# dashboard.net
KiCad netlist of a schematic drawn in EAGLE
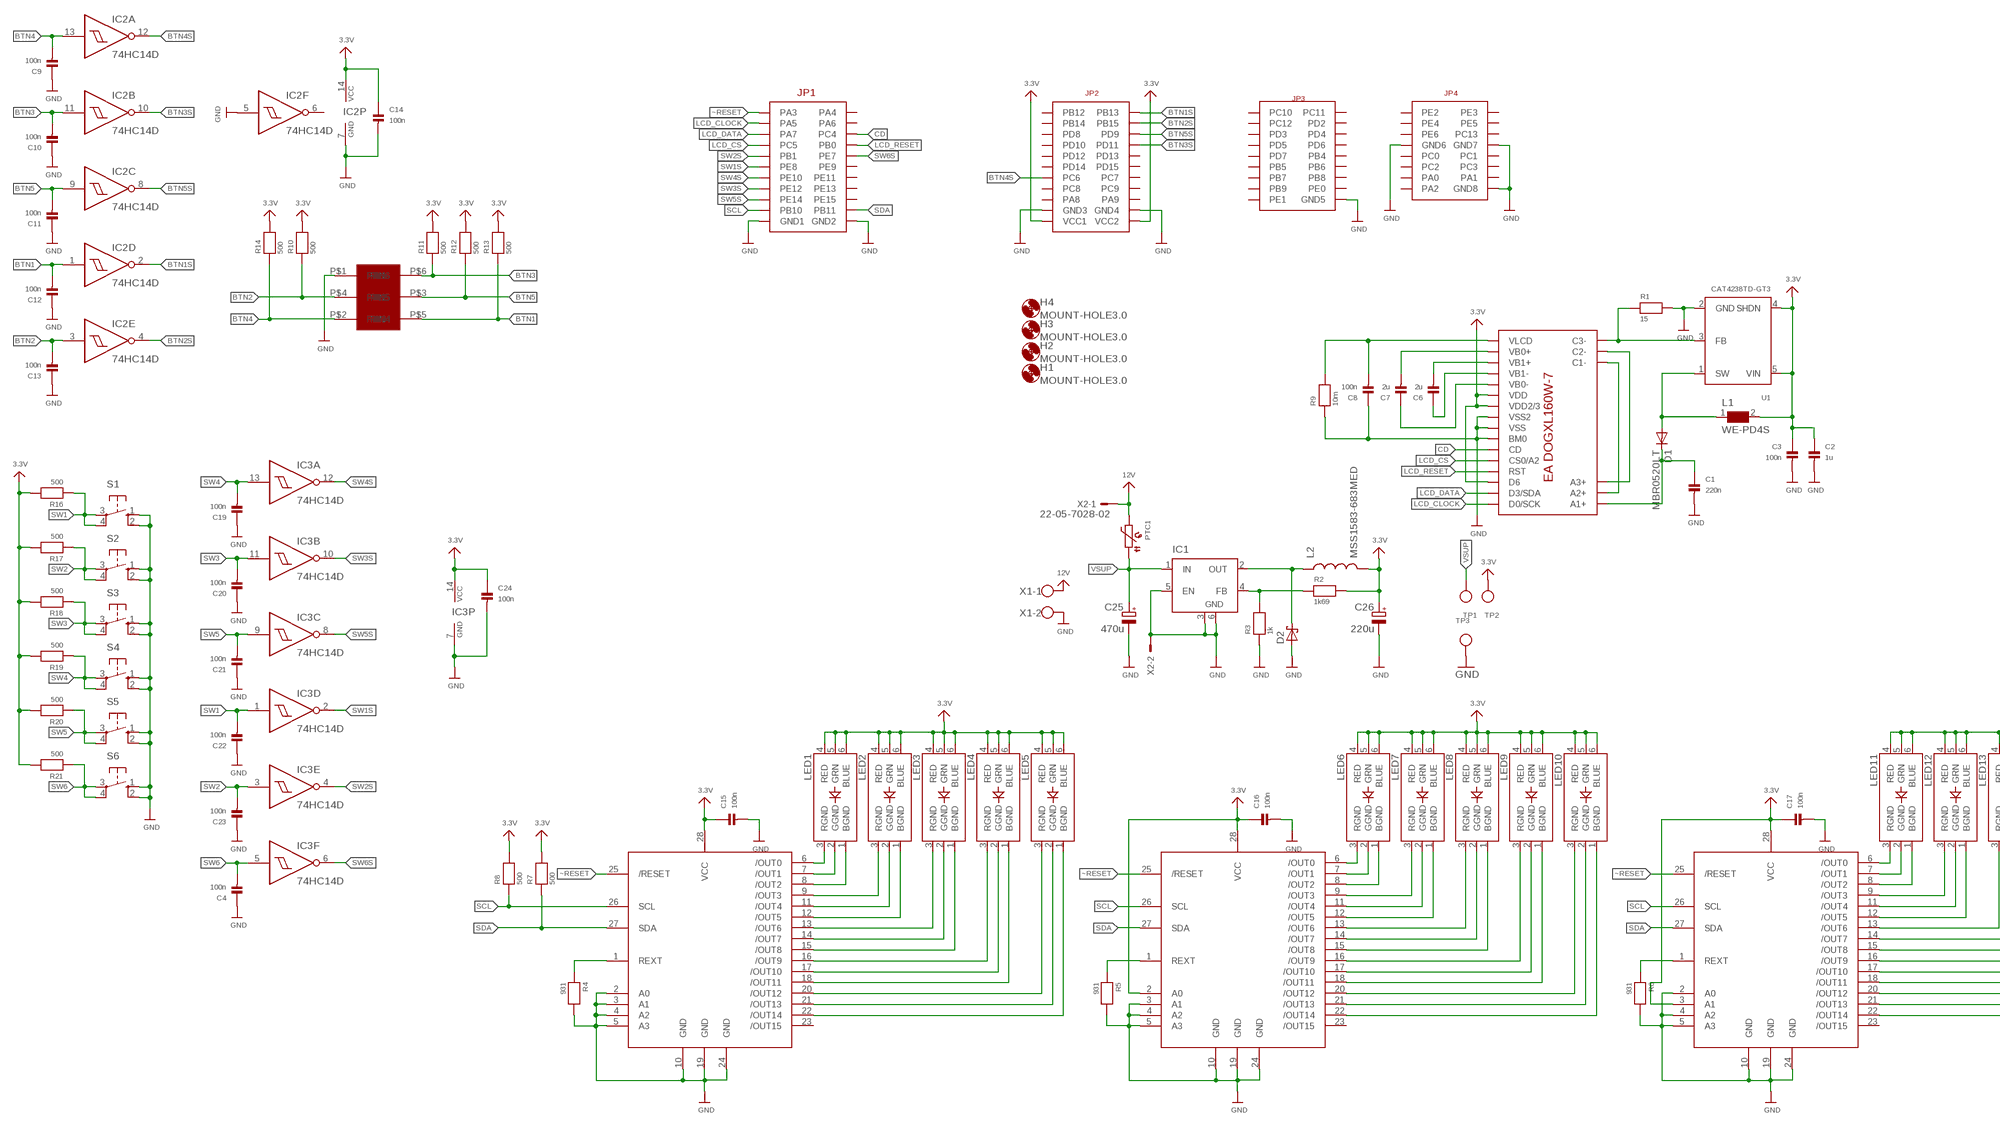
[diagram p0: schematic, sheet 1, part 1 of 2]
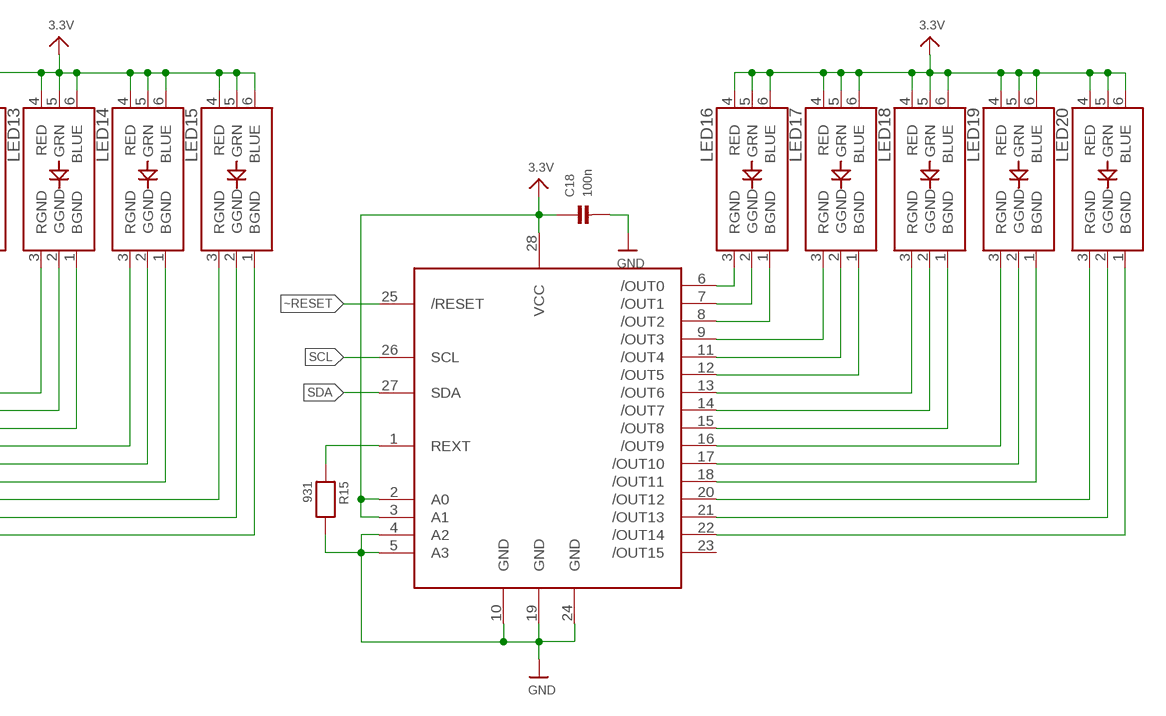
[diagram p1: schematic, sheet 1, part 2 of 2]

(export (version "E")
  (design (tool "Eeschema 10.0.6"))
  (components
    (comp (ref "C1")
      (value "220n")
      (footprint "eagle-import:_0805")
      (libsource (lib "eagle-import") (part "CAP_CERAMIC_0805"))
    )
    (comp (ref "C2")
      (value "1u")
      (footprint "eagle-import:_0805")
      (libsource (lib "eagle-import") (part "CAP_CERAMIC_0805"))
    )
    (comp (ref "C3")
      (value "100n")
      (footprint "eagle-import:_0603")
      (libsource (lib "eagle-import") (part "CAP_CERAMIC_0603"))
    )
    (comp (ref "C4")
      (value "100n")
      (footprint "eagle-import:_0603")
      (libsource (lib "eagle-import") (part "CAP_CERAMIC_0603"))
    )
    (comp (ref "C6")
      (value "2u")
      (footprint "eagle-import:_0805")
      (libsource (lib "eagle-import") (part "CAP_CERAMIC_0805"))
    )
    (comp (ref "C7")
      (value "2u")
      (footprint "eagle-import:_0805")
      (libsource (lib "eagle-import") (part "CAP_CERAMIC_0805"))
    )
    (comp (ref "C8")
      (value "100n")
      (footprint "eagle-import:_0603")
      (libsource (lib "eagle-import") (part "CAP_CERAMIC_0603"))
    )
    (comp (ref "C9")
      (value "100n")
      (footprint "eagle-import:_0603")
      (libsource (lib "eagle-import") (part "CAP_CERAMIC_0603"))
    )
    (comp (ref "C10")
      (value "100n")
      (footprint "eagle-import:_0603")
      (libsource (lib "eagle-import") (part "CAP_CERAMIC_0603"))
    )
    (comp (ref "C11")
      (value "100n")
      (footprint "eagle-import:_0603")
      (libsource (lib "eagle-import") (part "CAP_CERAMIC_0603"))
    )
    (comp (ref "C12")
      (value "100n")
      (footprint "eagle-import:_0603")
      (libsource (lib "eagle-import") (part "CAP_CERAMIC_0603"))
    )
    (comp (ref "C13")
      (value "100n")
      (footprint "eagle-import:_0603")
      (libsource (lib "eagle-import") (part "CAP_CERAMIC_0603"))
    )
    (comp (ref "C14")
      (value "100n")
      (footprint "eagle-import:_0603")
      (libsource (lib "eagle-import") (part "CAP_CERAMIC_0603"))
    )
    (comp (ref "C15")
      (value "100n")
      (footprint "eagle-import:_0603")
      (libsource (lib "eagle-import") (part "CAP_CERAMIC_0603"))
    )
    (comp (ref "C16")
      (value "100n")
      (footprint "eagle-import:_0603")
      (libsource (lib "eagle-import") (part "CAP_CERAMIC_0603"))
    )
    (comp (ref "C17")
      (value "100n")
      (footprint "eagle-import:_0603")
      (libsource (lib "eagle-import") (part "CAP_CERAMIC_0603"))
    )
    (comp (ref "C18")
      (value "100n")
      (footprint "eagle-import:_0603")
      (libsource (lib "eagle-import") (part "CAP_CERAMIC_0603"))
    )
    (comp (ref "C19")
      (value "100n")
      (footprint "eagle-import:_0603")
      (libsource (lib "eagle-import") (part "CAP_CERAMIC_0603"))
    )
    (comp (ref "C20")
      (value "100n")
      (footprint "eagle-import:_0603")
      (libsource (lib "eagle-import") (part "CAP_CERAMIC_0603"))
    )
    (comp (ref "C21")
      (value "100n")
      (footprint "eagle-import:_0603")
      (libsource (lib "eagle-import") (part "CAP_CERAMIC_0603"))
    )
    (comp (ref "C22")
      (value "100n")
      (footprint "eagle-import:_0603")
      (libsource (lib "eagle-import") (part "CAP_CERAMIC_0603"))
    )
    (comp (ref "C23")
      (value "100n")
      (footprint "eagle-import:_0603")
      (libsource (lib "eagle-import") (part "CAP_CERAMIC_0603"))
    )
    (comp (ref "C24")
      (value "100n")
      (footprint "eagle-import:_0603")
      (libsource (lib "eagle-import") (part "CAP_CERAMIC_0603"))
    )
    (comp (ref "C25")
      (value "470u")
      (footprint "eagle-import:153CLV-1012")
      (libsource (lib "eagle-import") (part "CPOL-EU153CLV-1012"))
    )
    (comp (ref "C26")
      (value "220u")
      (footprint "eagle-import:153CLV-1012")
      (libsource (lib "eagle-import") (part "CPOL-EU153CLV-1012"))
    )
    (comp (ref "D1")
      (value "MBR0520LT")
      (footprint "eagle-import:SOD123")
      (libsource (lib "eagle-import") (part "MBR0520LT"))
    )
    (comp (ref "D2")
      (value "SCHOTTKY-DIODESMC")
      (footprint "eagle-import:SMC")
      (libsource (lib "eagle-import") (part "SCHOTTKY-DIODESMC"))
    )
    (comp (ref "H1")
      (value "MOUNT-HOLE3.0")
      (footprint "eagle-import:3,0")
      (libsource (lib "eagle-import") (part "MOUNT-HOLE3.0"))
    )
    (comp (ref "H2")
      (value "MOUNT-HOLE3.0")
      (footprint "eagle-import:3,0")
      (libsource (lib "eagle-import") (part "MOUNT-HOLE3.0"))
    )
    (comp (ref "H3")
      (value "MOUNT-HOLE3.0")
      (footprint "eagle-import:3,0")
      (libsource (lib "eagle-import") (part "MOUNT-HOLE3.0"))
    )
    (comp (ref "H4")
      (value "MOUNT-HOLE3.0")
      (footprint "eagle-import:3,0")
      (libsource (lib "eagle-import") (part "MOUNT-HOLE3.0"))
    )
    (comp (ref "IC1")
      (value "LM2596S")
      (footprint "eagle-import:TO263-5")
      (libsource (lib "eagle-import") (part "LM2596S"))
    )
    (comp (ref "IC2")
      (value "74HC14D")
      (footprint "eagle-import:SO14")
      (libsource (lib "eagle-import") (part "7414DHC"))
    )
    (comp (ref "IC3")
      (value "74HC14D")
      (footprint "eagle-import:SO14")
      (libsource (lib "eagle-import") (part "7414DHC"))
    )
    (comp (ref "L1")
      (value "WE-PD4S")
      (footprint "eagle-import:S")
      (fields (field (name "MPN") "7445501"))
      (libsource (lib "eagle-import") (part "WE-PD4_S-7445501"))
    )
    (comp (ref "L2")
      (value "MSS1583-683MED")
      (footprint "eagle-import:CDRH125")
      (libsource (lib "eagle-import") (part "INDUCTORPWR"))
    )
    (comp (ref "LED1")
      (value "LED_RGB_PLCC6CREE-CLV6A")
      (footprint "eagle-import:RGBLED_PLCC6")
      (libsource (lib "eagle-import") (part "LED_RGB_PLCC6CREE-CLV6A"))
    )
    (comp (ref "LED2")
      (value "LED_RGB_PLCC6CREE-CLV6A")
      (footprint "eagle-import:RGBLED_PLCC6")
      (libsource (lib "eagle-import") (part "LED_RGB_PLCC6CREE-CLV6A"))
    )
    (comp (ref "LED3")
      (value "LED_RGB_PLCC6CREE-CLV6A")
      (footprint "eagle-import:RGBLED_PLCC6")
      (libsource (lib "eagle-import") (part "LED_RGB_PLCC6CREE-CLV6A"))
    )
    (comp (ref "LED4")
      (value "LED_RGB_PLCC6CREE-CLV6A")
      (footprint "eagle-import:RGBLED_PLCC6")
      (libsource (lib "eagle-import") (part "LED_RGB_PLCC6CREE-CLV6A"))
    )
    (comp (ref "LED5")
      (value "LED_RGB_PLCC6CREE-CLV6A")
      (footprint "eagle-import:RGBLED_PLCC6")
      (libsource (lib "eagle-import") (part "LED_RGB_PLCC6CREE-CLV6A"))
    )
    (comp (ref "LED6")
      (value "LED_RGB_PLCC6CREE-CLV6A")
      (footprint "eagle-import:RGBLED_PLCC6")
      (libsource (lib "eagle-import") (part "LED_RGB_PLCC6CREE-CLV6A"))
    )
    (comp (ref "LED7")
      (value "LED_RGB_PLCC6CREE-CLV6A")
      (footprint "eagle-import:RGBLED_PLCC6")
      (libsource (lib "eagle-import") (part "LED_RGB_PLCC6CREE-CLV6A"))
    )
    (comp (ref "LED8")
      (value "LED_RGB_PLCC6CREE-CLV6A")
      (footprint "eagle-import:RGBLED_PLCC6")
      (libsource (lib "eagle-import") (part "LED_RGB_PLCC6CREE-CLV6A"))
    )
    (comp (ref "LED9")
      (value "LED_RGB_PLCC6CREE-CLV6A")
      (footprint "eagle-import:RGBLED_PLCC6")
      (libsource (lib "eagle-import") (part "LED_RGB_PLCC6CREE-CLV6A"))
    )
    (comp (ref "LED10")
      (value "LED_RGB_PLCC6CREE-CLV6A")
      (footprint "eagle-import:RGBLED_PLCC6")
      (libsource (lib "eagle-import") (part "LED_RGB_PLCC6CREE-CLV6A"))
    )
    (comp (ref "LED11")
      (value "LED_RGB_PLCC6CREE-CLV6A")
      (footprint "eagle-import:RGBLED_PLCC6")
      (libsource (lib "eagle-import") (part "LED_RGB_PLCC6CREE-CLV6A"))
    )
    (comp (ref "LED12")
      (value "LED_RGB_PLCC6CREE-CLV6A")
      (footprint "eagle-import:RGBLED_PLCC6")
      (libsource (lib "eagle-import") (part "LED_RGB_PLCC6CREE-CLV6A"))
    )
    (comp (ref "LED13")
      (value "LED_RGB_PLCC6CREE-CLV6A")
      (footprint "eagle-import:RGBLED_PLCC6")
      (libsource (lib "eagle-import") (part "LED_RGB_PLCC6CREE-CLV6A"))
    )
    (comp (ref "LED14")
      (value "LED_RGB_PLCC6CREE-CLV6A")
      (footprint "eagle-import:RGBLED_PLCC6")
      (libsource (lib "eagle-import") (part "LED_RGB_PLCC6CREE-CLV6A"))
    )
    (comp (ref "LED15")
      (value "LED_RGB_PLCC6CREE-CLV6A")
      (footprint "eagle-import:RGBLED_PLCC6")
      (libsource (lib "eagle-import") (part "LED_RGB_PLCC6CREE-CLV6A"))
    )
    (comp (ref "LED16")
      (value "LED_RGB_PLCC6CREE-CLV6A")
      (footprint "eagle-import:RGBLED_PLCC6")
      (libsource (lib "eagle-import") (part "LED_RGB_PLCC6CREE-CLV6A"))
    )
    (comp (ref "LED17")
      (value "LED_RGB_PLCC6CREE-CLV6A")
      (footprint "eagle-import:RGBLED_PLCC6")
      (libsource (lib "eagle-import") (part "LED_RGB_PLCC6CREE-CLV6A"))
    )
    (comp (ref "LED18")
      (value "LED_RGB_PLCC6CREE-CLV6A")
      (footprint "eagle-import:RGBLED_PLCC6")
      (libsource (lib "eagle-import") (part "LED_RGB_PLCC6CREE-CLV6A"))
    )
    (comp (ref "LED19")
      (value "LED_RGB_PLCC6CREE-CLV6A")
      (footprint "eagle-import:RGBLED_PLCC6")
      (libsource (lib "eagle-import") (part "LED_RGB_PLCC6CREE-CLV6A"))
    )
    (comp (ref "LED20")
      (value "LED_RGB_PLCC6CREE-CLV6A")
      (footprint "eagle-import:RGBLED_PLCC6")
      (libsource (lib "eagle-import") (part "LED_RGB_PLCC6CREE-CLV6A"))
    )
    (comp (ref "PTC1")
      (value "PTC1812")
      (footprint "eagle-import:PTC1812")
      (libsource (lib "eagle-import") (part "PTC1812"))
    )
    (comp (ref "R1")
      (value "15")
      (footprint "eagle-import:_0603")
      (libsource (lib "eagle-import") (part "RESISTOR_0603"))
    )
    (comp (ref "R2")
      (value "1k69")
      (footprint "eagle-import:_0603")
      (libsource (lib "eagle-import") (part "RESISTOR_0603"))
    )
    (comp (ref "R3")
      (value "1k")
      (footprint "eagle-import:_0603")
      (libsource (lib "eagle-import") (part "RESISTOR_0603"))
    )
    (comp (ref "R4")
      (value "931")
      (footprint "eagle-import:_0603")
      (libsource (lib "eagle-import") (part "RESISTOR_0603"))
    )
    (comp (ref "R5")
      (value "931")
      (footprint "eagle-import:_0603")
      (libsource (lib "eagle-import") (part "RESISTOR_0603"))
    )
    (comp (ref "R6")
      (value "931")
      (footprint "eagle-import:_0603")
      (libsource (lib "eagle-import") (part "RESISTOR_0603"))
    )
    (comp (ref "R7")
      (value "500")
      (footprint "eagle-import:_0603")
      (libsource (lib "eagle-import") (part "RESISTOR_0603"))
    )
    (comp (ref "R8")
      (value "500")
      (footprint "eagle-import:_0603")
      (libsource (lib "eagle-import") (part "RESISTOR_0603"))
    )
    (comp (ref "R9")
      (value "10m")
      (footprint "eagle-import:_0805")
      (libsource (lib "eagle-import") (part "RESISTOR_0805"))
    )
    (comp (ref "R10")
      (value "500")
      (footprint "eagle-import:_0603")
      (libsource (lib "eagle-import") (part "RESISTOR_0603"))
    )
    (comp (ref "R11")
      (value "500")
      (footprint "eagle-import:_0603")
      (libsource (lib "eagle-import") (part "RESISTOR_0603"))
    )
    (comp (ref "R12")
      (value "500")
      (footprint "eagle-import:_0603")
      (libsource (lib "eagle-import") (part "RESISTOR_0603"))
    )
    (comp (ref "R13")
      (value "500")
      (footprint "eagle-import:_0603")
      (libsource (lib "eagle-import") (part "RESISTOR_0603"))
    )
    (comp (ref "R14")
      (value "500")
      (footprint "eagle-import:_0603")
      (libsource (lib "eagle-import") (part "RESISTOR_0603"))
    )
    (comp (ref "R15")
      (value "931")
      (footprint "eagle-import:_0603")
      (libsource (lib "eagle-import") (part "RESISTOR_0603"))
    )
    (comp (ref "R16")
      (value "500")
      (footprint "eagle-import:_0603")
      (libsource (lib "eagle-import") (part "RESISTOR_0603"))
    )
    (comp (ref "R17")
      (value "500")
      (footprint "eagle-import:_0603")
      (libsource (lib "eagle-import") (part "RESISTOR_0603"))
    )
    (comp (ref "R18")
      (value "500")
      (footprint "eagle-import:_0603")
      (libsource (lib "eagle-import") (part "RESISTOR_0603"))
    )
    (comp (ref "R19")
      (value "500")
      (footprint "eagle-import:_0603")
      (libsource (lib "eagle-import") (part "RESISTOR_0603"))
    )
    (comp (ref "R20")
      (value "500")
      (footprint "eagle-import:_0603")
      (libsource (lib "eagle-import") (part "RESISTOR_0603"))
    )
    (comp (ref "R21")
      (value "500")
      (footprint "eagle-import:_0603")
      (libsource (lib "eagle-import") (part "RESISTOR_0603"))
    )
    (comp (ref "S1")
      (value "10-XX")
      (footprint "eagle-import:B3F-10XX")
      (fields (field (name "MPN") "B3F-1000"))
      (libsource (lib "eagle-import") (part "10-XX"))
    )
    (comp (ref "S2")
      (value "10-XX")
      (footprint "eagle-import:B3F-10XX")
      (fields (field (name "MPN") "B3F-1000"))
      (libsource (lib "eagle-import") (part "10-XX"))
    )
    (comp (ref "S3")
      (value "10-XX")
      (footprint "eagle-import:B3F-10XX")
      (fields (field (name "MPN") "B3F-1000"))
      (libsource (lib "eagle-import") (part "10-XX"))
    )
    (comp (ref "S4")
      (value "10-XX")
      (footprint "eagle-import:B3F-10XX")
      (fields (field (name "MPN") "B3F-1000"))
      (libsource (lib "eagle-import") (part "10-XX"))
    )
    (comp (ref "S5")
      (value "10-XX")
      (footprint "eagle-import:B3F-10XX")
      (fields
        (field (name "MPN") "B3F-1000")
        (field (name "MPN_1") "B3F-1000")
        (field (name "OC_FARNELL") "176432")
        (field (name "OC_NEWARK") "36M3542")
      )
      (libsource (lib "eagle-import") (part "10-XX"))
    )
    (comp (ref "S6")
      (value "10-XX")
      (footprint "eagle-import:B3F-10XX")
      (fields
        (field (name "MPN") "B3F-1000")
        (field (name "MPN_1") "B3F-1000")
        (field (name "OC_FARNELL") "176432")
        (field (name "OC_NEWARK") "36M3542")
      )
      (libsource (lib "eagle-import") (part "10-XX"))
    )
    (comp (ref "TP1")
      (value "TESTPOINT")
      (footprint "eagle-import:TESTPOINT_SMT")
      (libsource (lib "eagle-import") (part "TESTPOINT"))
    )
    (comp (ref "TP2")
      (value "TESTPOINT")
      (footprint "eagle-import:TESTPOINT_SMT")
      (libsource (lib "eagle-import") (part "TESTPOINT"))
    )
    (comp (ref "TP3")
      (value "TESTPOINT")
      (footprint "eagle-import:TESTPOINT_SMT")
      (libsource (lib "eagle-import") (part "TESTPOINT"))
    )
    (comp (ref "U$1")
      (value "CPU-BOARD")
      (footprint "eagle-import:CPU-BOARD-JP1")
      (libsource (lib "eagle-import") (part "CPU-BOARD"))
    )
    (comp (ref "U$10")
      (value "EA-DOGXL160W-7")
      (footprint "eagle-import:EA-DOGXL160W-7")
      (libsource (lib "eagle-import") (part "EA-DOGXL160W-7"))
    )
    (comp (ref "U$30")
      (value "TLC59116")
      (footprint "eagle-import:TSSOP28")
      (libsource (lib "eagle-import") (part "TLC59116"))
    )
    (comp (ref "U$33")
      (value "TLC59116")
      (footprint "eagle-import:TSSOP28")
      (libsource (lib "eagle-import") (part "TLC59116"))
    )
    (comp (ref "U$36")
      (value "TLC59116")
      (footprint "eagle-import:TSSOP28")
      (libsource (lib "eagle-import") (part "TLC59116"))
    )
    (comp (ref "U$42")
      (value "MICROFIT6")
      (footprint "eagle-import:43045-0600")
      (libsource (lib "eagle-import") (part "MICROFIT6"))
    )
    (comp (ref "U$51")
      (value "TLC59116")
      (footprint "eagle-import:TSSOP28")
      (libsource (lib "eagle-import") (part "TLC59116"))
    )
    (comp (ref "U1")
      (value "CAT4238TD-GT3")
      (footprint "eagle-import:SOT23-5")
      (libsource (lib "eagle-import") (part "FAN5331"))
    )
    (comp (ref "X1")
      (value "W237-102")
      (footprint "eagle-import:W237-102")
      (fields (field (name "MPN") "237-102"))
      (libsource (lib "eagle-import") (part "W237-102"))
    )
    (comp (ref "X2")
      (value "22-05-7028-02")
      (footprint "eagle-import:7395-02")
      (fields (field (name "OC_FARNELL") "9731601") (field (name "OC_NEWARK") "unknown"))
      (libsource (lib "eagle-import") (part "22-?-0205-7028"))
    )
  )
  (nets
    (net (code "1") (name "/~{RESET}") (class "Default")
      (node (ref "U$1") (pin "P$1") (pinfunction "PA3_P$1") (pintype "bidirectional"))
      (node (ref "U$30") (pin "25") (pinfunction "/RESET_25") (pintype "bidirectional"))
      (node (ref "U$33") (pin "25") (pinfunction "/RESET_25") (pintype "bidirectional"))
      (node (ref "U$36") (pin "25") (pinfunction "/RESET_25") (pintype "bidirectional"))
      (node (ref "U$51") (pin "25") (pinfunction "/RESET_25") (pintype "bidirectional"))
    )
    (net (code "2") (name "3.3V") (class "Default")
      (node (ref "C14") (pin "1") (pinfunction "P$1_1") (pintype "passive"))
      (node (ref "C15") (pin "1") (pinfunction "P$1_1") (pintype "passive"))
      (node (ref "C16") (pin "1") (pinfunction "P$1_1") (pintype "passive"))
      (node (ref "C17") (pin "1") (pinfunction "P$1_1") (pintype "passive"))
      (node (ref "C18") (pin "1") (pinfunction "P$1_1") (pintype "passive"))
      (node (ref "C2") (pin "1") (pinfunction "P$1_1") (pintype "passive"))
      (node (ref "C24") (pin "1") (pinfunction "P$1_1") (pintype "passive"))
      (node (ref "C26") (pin "+") (pinfunction "+_+") (pintype "passive"))
      (node (ref "C3") (pin "1") (pinfunction "P$1_1") (pintype "passive"))
      (node (ref "IC2") (pin "14") (pinfunction "VCC_14") (pintype "power_in"))
      (node (ref "IC3") (pin "14") (pinfunction "VCC_14") (pintype "power_in"))
      (node (ref "L1") (pin "2") (pinfunction "2_2") (pintype "passive"))
      (node (ref "L2") (pin "2") (pinfunction "2_2") (pintype "passive"))
      (node (ref "LED1") (pin "4") (pinfunction "RED_4") (pintype "bidirectional"))
      (node (ref "LED1") (pin "5") (pinfunction "GRN_5") (pintype "bidirectional"))
      (node (ref "LED1") (pin "6") (pinfunction "BLUE_6") (pintype "bidirectional"))
      (node (ref "LED10") (pin "4") (pinfunction "RED_4") (pintype "bidirectional"))
      (node (ref "LED10") (pin "5") (pinfunction "GRN_5") (pintype "bidirectional"))
      (node (ref "LED10") (pin "6") (pinfunction "BLUE_6") (pintype "bidirectional"))
      (node (ref "LED11") (pin "4") (pinfunction "RED_4") (pintype "bidirectional"))
      (node (ref "LED11") (pin "5") (pinfunction "GRN_5") (pintype "bidirectional"))
      (node (ref "LED11") (pin "6") (pinfunction "BLUE_6") (pintype "bidirectional"))
      (node (ref "LED12") (pin "4") (pinfunction "RED_4") (pintype "bidirectional"))
      (node (ref "LED12") (pin "5") (pinfunction "GRN_5") (pintype "bidirectional"))
      (node (ref "LED12") (pin "6") (pinfunction "BLUE_6") (pintype "bidirectional"))
      (node (ref "LED13") (pin "4") (pinfunction "RED_4") (pintype "bidirectional"))
      (node (ref "LED13") (pin "5") (pinfunction "GRN_5") (pintype "bidirectional"))
      (node (ref "LED13") (pin "6") (pinfunction "BLUE_6") (pintype "bidirectional"))
      (node (ref "LED14") (pin "4") (pinfunction "RED_4") (pintype "bidirectional"))
      (node (ref "LED14") (pin "5") (pinfunction "GRN_5") (pintype "bidirectional"))
      (node (ref "LED14") (pin "6") (pinfunction "BLUE_6") (pintype "bidirectional"))
      (node (ref "LED15") (pin "4") (pinfunction "RED_4") (pintype "bidirectional"))
      (node (ref "LED15") (pin "5") (pinfunction "GRN_5") (pintype "bidirectional"))
      (node (ref "LED15") (pin "6") (pinfunction "BLUE_6") (pintype "bidirectional"))
      (node (ref "LED16") (pin "4") (pinfunction "RED_4") (pintype "bidirectional"))
      (node (ref "LED16") (pin "5") (pinfunction "GRN_5") (pintype "bidirectional"))
      (node (ref "LED16") (pin "6") (pinfunction "BLUE_6") (pintype "bidirectional"))
      (node (ref "LED17") (pin "4") (pinfunction "RED_4") (pintype "bidirectional"))
      (node (ref "LED17") (pin "5") (pinfunction "GRN_5") (pintype "bidirectional"))
      (node (ref "LED17") (pin "6") (pinfunction "BLUE_6") (pintype "bidirectional"))
      (node (ref "LED18") (pin "4") (pinfunction "RED_4") (pintype "bidirectional"))
      (node (ref "LED18") (pin "5") (pinfunction "GRN_5") (pintype "bidirectional"))
      (node (ref "LED18") (pin "6") (pinfunction "BLUE_6") (pintype "bidirectional"))
      (node (ref "LED19") (pin "4") (pinfunction "RED_4") (pintype "bidirectional"))
      (node (ref "LED19") (pin "5") (pinfunction "GRN_5") (pintype "bidirectional"))
      (node (ref "LED19") (pin "6") (pinfunction "BLUE_6") (pintype "bidirectional"))
      (node (ref "LED2") (pin "4") (pinfunction "RED_4") (pintype "bidirectional"))
      (node (ref "LED2") (pin "5") (pinfunction "GRN_5") (pintype "bidirectional"))
      (node (ref "LED2") (pin "6") (pinfunction "BLUE_6") (pintype "bidirectional"))
      (node (ref "LED20") (pin "4") (pinfunction "RED_4") (pintype "bidirectional"))
      (node (ref "LED20") (pin "5") (pinfunction "GRN_5") (pintype "bidirectional"))
      (node (ref "LED20") (pin "6") (pinfunction "BLUE_6") (pintype "bidirectional"))
      (node (ref "LED3") (pin "4") (pinfunction "RED_4") (pintype "bidirectional"))
      (node (ref "LED3") (pin "5") (pinfunction "GRN_5") (pintype "bidirectional"))
      (node (ref "LED3") (pin "6") (pinfunction "BLUE_6") (pintype "bidirectional"))
      (node (ref "LED4") (pin "4") (pinfunction "RED_4") (pintype "bidirectional"))
      (node (ref "LED4") (pin "5") (pinfunction "GRN_5") (pintype "bidirectional"))
      (node (ref "LED4") (pin "6") (pinfunction "BLUE_6") (pintype "bidirectional"))
      (node (ref "LED5") (pin "4") (pinfunction "RED_4") (pintype "bidirectional"))
      (node (ref "LED5") (pin "5") (pinfunction "GRN_5") (pintype "bidirectional"))
      (node (ref "LED5") (pin "6") (pinfunction "BLUE_6") (pintype "bidirectional"))
      (node (ref "LED6") (pin "4") (pinfunction "RED_4") (pintype "bidirectional"))
      (node (ref "LED6") (pin "5") (pinfunction "GRN_5") (pintype "bidirectional"))
      (node (ref "LED6") (pin "6") (pinfunction "BLUE_6") (pintype "bidirectional"))
      (node (ref "LED7") (pin "4") (pinfunction "RED_4") (pintype "bidirectional"))
      (node (ref "LED7") (pin "5") (pinfunction "GRN_5") (pintype "bidirectional"))
      (node (ref "LED7") (pin "6") (pinfunction "BLUE_6") (pintype "bidirectional"))
      (node (ref "LED8") (pin "4") (pinfunction "RED_4") (pintype "bidirectional"))
      (node (ref "LED8") (pin "5") (pinfunction "GRN_5") (pintype "bidirectional"))
      (node (ref "LED8") (pin "6") (pinfunction "BLUE_6") (pintype "bidirectional"))
      (node (ref "LED9") (pin "4") (pinfunction "RED_4") (pintype "bidirectional"))
      (node (ref "LED9") (pin "5") (pinfunction "GRN_5") (pintype "bidirectional"))
      (node (ref "LED9") (pin "6") (pinfunction "BLUE_6") (pintype "bidirectional"))
      (node (ref "R10") (pin "2") (pinfunction "2_2") (pintype "passive"))
      (node (ref "R11") (pin "2") (pinfunction "2_2") (pintype "passive"))
      (node (ref "R12") (pin "2") (pinfunction "2_2") (pintype "passive"))
      (node (ref "R13") (pin "2") (pinfunction "2_2") (pintype "passive"))
      (node (ref "R14") (pin "2") (pinfunction "2_2") (pintype "passive"))
      (node (ref "R16") (pin "2") (pinfunction "2_2") (pintype "passive"))
      (node (ref "R17") (pin "2") (pinfunction "2_2") (pintype "passive"))
      (node (ref "R18") (pin "2") (pinfunction "2_2") (pintype "passive"))
      (node (ref "R19") (pin "2") (pinfunction "2_2") (pintype "passive"))
      (node (ref "R2") (pin "2") (pinfunction "2_2") (pintype "passive"))
      (node (ref "R20") (pin "2") (pinfunction "2_2") (pintype "passive"))
      (node (ref "R21") (pin "2") (pinfunction "2_2") (pintype "passive"))
      (node (ref "R7") (pin "2") (pinfunction "2_2") (pintype "passive"))
      (node (ref "R8") (pin "2") (pinfunction "2_2") (pintype "passive"))
      (node (ref "TP2") (pin "P$1") (pinfunction "P$1_P$1") (pintype "bidirectional"))
      (node (ref "U$1") (pin "P$43") (pinfunction "VCC1_P$43") (pintype "bidirectional"))
      (node (ref "U$1") (pin "P$44") (pinfunction "VCC2_P$44") (pintype "bidirectional"))
      (node (ref "U$10") (pin "P$22") (pinfunction "VDD_P$22") (pintype "bidirectional"))
      (node (ref "U$10") (pin "P$23") (pinfunction "VDD2/3_P$23") (pintype "bidirectional"))
      (node (ref "U$10") (pin "P$30") (pinfunction "D6_P$30") (pintype "bidirectional"))
      (node (ref "U$30") (pin "28") (pinfunction "VCC_28") (pintype "bidirectional"))
      (node (ref "U$33") (pin "2") (pinfunction "A0_2") (pintype "bidirectional"))
      (node (ref "U$33") (pin "28") (pinfunction "VCC_28") (pintype "bidirectional"))
      (node (ref "U$36") (pin "28") (pinfunction "VCC_28") (pintype "bidirectional"))
      (node (ref "U$36") (pin "3") (pinfunction "A1_3") (pintype "bidirectional"))
      (node (ref "U$51") (pin "2") (pinfunction "A0_2") (pintype "bidirectional"))
      (node (ref "U$51") (pin "28") (pinfunction "VCC_28") (pintype "bidirectional"))
      (node (ref "U$51") (pin "3") (pinfunction "A1_3") (pintype "bidirectional"))
      (node (ref "U1") (pin "4") (pinfunction "SHDN_4") (pintype "bidirectional"))
      (node (ref "U1") (pin "5") (pinfunction "VIN_5") (pintype "bidirectional"))
    )
    (net (code "3") (name "12V") (class "Default")
      (node (ref "PTC1") (pin "P$2") (pinfunction "2_P$2") (pintype "passive"))
      (node (ref "X1") (pin "1") (pinfunction "KL_1") (pintype "passive"))
      (node (ref "X2") (pin "1") (pinfunction "S_1") (pintype "passive"))
    )
    (net (code "4") (name "BTN1") (class "Default")
      (node (ref "C12") (pin "2") (pinfunction "P$2_2") (pintype "passive"))
      (node (ref "IC2") (pin "1") (pinfunction "I_1") (pintype "input"))
      (node (ref "R13") (pin "1") (pinfunction "1_1") (pintype "passive"))
      (node (ref "U$42") (pin "P$5") (pinfunction "PIN4_P$5") (pintype "bidirectional"))
    )
    (net (code "5") (name "BTN1S") (class "Default")
      (node (ref "IC2") (pin "2") (pinfunction "O_2") (pintype "output"))
      (node (ref "U$1") (pin "P$24") (pinfunction "PB13_P$24") (pintype "bidirectional"))
    )
    (net (code "6") (name "BTN2") (class "Default")
      (node (ref "C13") (pin "2") (pinfunction "P$2_2") (pintype "passive"))
      (node (ref "IC2") (pin "3") (pinfunction "I_3") (pintype "input"))
      (node (ref "R10") (pin "1") (pinfunction "1_1") (pintype "passive"))
      (node (ref "U$42") (pin "P$4") (pinfunction "PIN2_P$4") (pintype "bidirectional"))
    )
    (net (code "7") (name "BTN2S") (class "Default")
      (node (ref "IC2") (pin "4") (pinfunction "O_4") (pintype "output"))
      (node (ref "U$1") (pin "P$26") (pinfunction "PB15_P$26") (pintype "bidirectional"))
    )
    (net (code "8") (name "BTN3") (class "Default")
      (node (ref "C10") (pin "2") (pinfunction "P$2_2") (pintype "passive"))
      (node (ref "IC2") (pin "11") (pinfunction "I_11") (pintype "input"))
      (node (ref "R11") (pin "1") (pinfunction "1_1") (pintype "passive"))
      (node (ref "U$42") (pin "P$6") (pinfunction "PIN6_P$6") (pintype "bidirectional"))
    )
    (net (code "9") (name "BTN3S") (class "Default")
      (node (ref "IC2") (pin "10") (pinfunction "O_10") (pintype "output"))
      (node (ref "U$1") (pin "P$30") (pinfunction "PD11_P$30") (pintype "bidirectional"))
    )
    (net (code "10") (name "BTN4") (class "Default")
      (node (ref "C9") (pin "2") (pinfunction "P$2_2") (pintype "passive"))
      (node (ref "IC2") (pin "13") (pinfunction "I_13") (pintype "input"))
      (node (ref "R14") (pin "1") (pinfunction "1_1") (pintype "passive"))
      (node (ref "U$42") (pin "P$2") (pinfunction "PIN3_P$2") (pintype "bidirectional"))
    )
    (net (code "11") (name "BTN4S") (class "Default")
      (node (ref "IC2") (pin "12") (pinfunction "O_12") (pintype "output"))
      (node (ref "U$1") (pin "P$35") (pinfunction "PC6_P$35") (pintype "bidirectional"))
    )
    (net (code "12") (name "BTN5") (class "Default")
      (node (ref "C11") (pin "2") (pinfunction "P$2_2") (pintype "passive"))
      (node (ref "IC2") (pin "9") (pinfunction "I_9") (pintype "input"))
      (node (ref "R12") (pin "1") (pinfunction "1_1") (pintype "passive"))
      (node (ref "U$42") (pin "P$3") (pinfunction "PIN5_P$3") (pintype "bidirectional"))
    )
    (net (code "13") (name "BTN5S") (class "Default")
      (node (ref "IC2") (pin "8") (pinfunction "O_8") (pintype "output"))
      (node (ref "U$1") (pin "P$28") (pinfunction "PD9_P$28") (pintype "bidirectional"))
    )
    (net (code "14") (name "CD") (class "Default")
      (node (ref "U$1") (pin "P$6") (pinfunction "PC4_P$6") (pintype "bidirectional"))
      (node (ref "U$10") (pin "P$27") (pinfunction "CD_P$27") (pintype "bidirectional"))
    )
    (net (code "15") (name "GND") (class "Default")
      (node (ref "C1") (pin "2") (pinfunction "P$2_2") (pintype "passive"))
      (node (ref "C10") (pin "1") (pinfunction "P$1_1") (pintype "passive"))
      (node (ref "C11") (pin "1") (pinfunction "P$1_1") (pintype "passive"))
      (node (ref "C12") (pin "1") (pinfunction "P$1_1") (pintype "passive"))
      (node (ref "C13") (pin "1") (pinfunction "P$1_1") (pintype "passive"))
      (node (ref "C14") (pin "2") (pinfunction "P$2_2") (pintype "passive"))
      (node (ref "C15") (pin "2") (pinfunction "P$2_2") (pintype "passive"))
      (node (ref "C16") (pin "2") (pinfunction "P$2_2") (pintype "passive"))
      (node (ref "C17") (pin "2") (pinfunction "P$2_2") (pintype "passive"))
      (node (ref "C18") (pin "2") (pinfunction "P$2_2") (pintype "passive"))
      (node (ref "C19") (pin "1") (pinfunction "P$1_1") (pintype "passive"))
      (node (ref "C2") (pin "2") (pinfunction "P$2_2") (pintype "passive"))
      (node (ref "C20") (pin "1") (pinfunction "P$1_1") (pintype "passive"))
      (node (ref "C21") (pin "1") (pinfunction "P$1_1") (pintype "passive"))
      (node (ref "C22") (pin "1") (pinfunction "P$1_1") (pintype "passive"))
      (node (ref "C23") (pin "1") (pinfunction "P$1_1") (pintype "passive"))
      (node (ref "C24") (pin "2") (pinfunction "P$2_2") (pintype "passive"))
      (node (ref "C25") (pin "-") (pinfunction "-_-") (pintype "passive"))
      (node (ref "C26") (pin "-") (pinfunction "-_-") (pintype "passive"))
      (node (ref "C3") (pin "2") (pinfunction "P$2_2") (pintype "passive"))
      (node (ref "C4") (pin "1") (pinfunction "P$1_1") (pintype "passive"))
      (node (ref "C8") (pin "1") (pinfunction "P$1_1") (pintype "passive"))
      (node (ref "C9") (pin "1") (pinfunction "P$1_1") (pintype "passive"))
      (node (ref "D2") (pin "A") (pinfunction "A_A") (pintype "passive"))
      (node (ref "IC1") (pin "3") (pinfunction "GND_3") (pintype "power_in"))
      (node (ref "IC1") (pin "5") (pinfunction "EN_5") (pintype "input"))
      (node (ref "IC1") (pin "6") (pinfunction "GND_6") (pintype "power_in"))
      (node (ref "IC2") (pin "5") (pinfunction "I_5") (pintype "input"))
      (node (ref "IC2") (pin "7") (pinfunction "GND_7") (pintype "power_in"))
      (node (ref "IC3") (pin "7") (pinfunction "GND_7") (pintype "power_in"))
      (node (ref "R1") (pin "2") (pinfunction "2_2") (pintype "passive"))
      (node (ref "R15") (pin "2") (pinfunction "2_2") (pintype "passive"))
      (node (ref "R3") (pin "1") (pinfunction "1_1") (pintype "passive"))
      (node (ref "R4") (pin "2") (pinfunction "2_2") (pintype "passive"))
      (node (ref "R5") (pin "2") (pinfunction "2_2") (pintype "passive"))
      (node (ref "R6") (pin "2") (pinfunction "2_2") (pintype "passive"))
      (node (ref "R9") (pin "1") (pinfunction "1_1") (pintype "passive"))
      (node (ref "S1") (pin "1") (pinfunction "S_1") (pintype "passive"))
      (node (ref "S1") (pin "2") (pinfunction "S1_2") (pintype "passive"))
      (node (ref "S2") (pin "1") (pinfunction "S_1") (pintype "passive"))
      (node (ref "S2") (pin "2") (pinfunction "S1_2") (pintype "passive"))
      (node (ref "S3") (pin "1") (pinfunction "S_1") (pintype "passive"))
      (node (ref "S3") (pin "2") (pinfunction "S1_2") (pintype "passive"))
      (node (ref "S4") (pin "1") (pinfunction "S_1") (pintype "passive"))
      (node (ref "S4") (pin "2") (pinfunction "S1_2") (pintype "passive"))
      (node (ref "S5") (pin "1") (pinfunction "S_1") (pintype "passive"))
      (node (ref "S5") (pin "2") (pinfunction "S1_2") (pintype "passive"))
      (node (ref "S6") (pin "1") (pinfunction "S_1") (pintype "passive"))
      (node (ref "S6") (pin "2") (pinfunction "S1_2") (pintype "passive"))
      (node (ref "TP3") (pin "P$1") (pinfunction "P$1_P$1") (pintype "bidirectional"))
      (node (ref "U$1") (pin "P$19") (pinfunction "GND1_P$19") (pintype "bidirectional"))
      (node (ref "U$1") (pin "P$20") (pinfunction "GND2_P$20") (pintype "bidirectional"))
      (node (ref "U$1") (pin "P$41") (pinfunction "GND3_P$41") (pintype "bidirectional"))
      (node (ref "U$1") (pin "P$42") (pinfunction "GND4_P$42") (pintype "bidirectional"))
      (node (ref "U$1") (pin "P$62") (pinfunction "GND5_P$62") (pintype "bidirectional"))
      (node (ref "U$1") (pin "P$69") (pinfunction "GND6_P$69") (pintype "bidirectional"))
      (node (ref "U$1") (pin "P$70") (pinfunction "GND7_P$70") (pintype "bidirectional"))
      (node (ref "U$1") (pin "P$78") (pinfunction "GND8_P$78") (pintype "bidirectional"))
      (node (ref "U$10") (pin "P$24") (pinfunction "VSS2_P$24") (pintype "bidirectional"))
      (node (ref "U$10") (pin "P$25") (pinfunction "VSS_P$25") (pintype "bidirectional"))
      (node (ref "U$10") (pin "P$26") (pinfunction "BM0_P$26") (pintype "bidirectional"))
      (node (ref "U$30") (pin "10") (pinfunction "GND_10") (pintype "bidirectional"))
      (node (ref "U$30") (pin "19") (pinfunction "GND_19") (pintype "bidirectional"))
      (node (ref "U$30") (pin "2") (pinfunction "A0_2") (pintype "bidirectional"))
      (node (ref "U$30") (pin "24") (pinfunction "GND_24") (pintype "bidirectional"))
      (node (ref "U$30") (pin "3") (pinfunction "A1_3") (pintype "bidirectional"))
      (node (ref "U$30") (pin "4") (pinfunction "A2_4") (pintype "bidirectional"))
      (node (ref "U$30") (pin "5") (pinfunction "A3_5") (pintype "bidirectional"))
      (node (ref "U$33") (pin "10") (pinfunction "GND_10") (pintype "bidirectional"))
      (node (ref "U$33") (pin "19") (pinfunction "GND_19") (pintype "bidirectional"))
      (node (ref "U$33") (pin "24") (pinfunction "GND_24") (pintype "bidirectional"))
      (node (ref "U$33") (pin "3") (pinfunction "A1_3") (pintype "bidirectional"))
      (node (ref "U$33") (pin "4") (pinfunction "A2_4") (pintype "bidirectional"))
      (node (ref "U$33") (pin "5") (pinfunction "A3_5") (pintype "bidirectional"))
      (node (ref "U$36") (pin "10") (pinfunction "GND_10") (pintype "bidirectional"))
      (node (ref "U$36") (pin "19") (pinfunction "GND_19") (pintype "bidirectional"))
      (node (ref "U$36") (pin "2") (pinfunction "A0_2") (pintype "bidirectional"))
      (node (ref "U$36") (pin "24") (pinfunction "GND_24") (pintype "bidirectional"))
      (node (ref "U$36") (pin "4") (pinfunction "A2_4") (pintype "bidirectional"))
      (node (ref "U$36") (pin "5") (pinfunction "A3_5") (pintype "bidirectional"))
      (node (ref "U$42") (pin "P$1") (pinfunction "PIN1_P$1") (pintype "bidirectional"))
      (node (ref "U$51") (pin "10") (pinfunction "GND_10") (pintype "bidirectional"))
      (node (ref "U$51") (pin "19") (pinfunction "GND_19") (pintype "bidirectional"))
      (node (ref "U$51") (pin "24") (pinfunction "GND_24") (pintype "bidirectional"))
      (node (ref "U$51") (pin "4") (pinfunction "A2_4") (pintype "bidirectional"))
      (node (ref "U$51") (pin "5") (pinfunction "A3_5") (pintype "bidirectional"))
      (node (ref "U1") (pin "2") (pinfunction "GND_2") (pintype "bidirectional"))
      (node (ref "X1") (pin "2") (pinfunction "KL_2") (pintype "passive"))
      (node (ref "X2") (pin "2") (pinfunction "S_2") (pintype "passive"))
    )
    (net (code "16") (name "LCD_CLOCK") (class "Default")
      (node (ref "U$1") (pin "P$3") (pinfunction "PA5_P$3") (pintype "bidirectional"))
      (node (ref "U$10") (pin "P$32") (pinfunction "D0/SCK_P$32") (pintype "bidirectional"))
    )
    (net (code "17") (name "LCD_CS") (class "Default")
      (node (ref "U$1") (pin "P$7") (pinfunction "PC5_P$7") (pintype "bidirectional"))
      (node (ref "U$10") (pin "P$28") (pinfunction "CS0/A2_P$28") (pintype "bidirectional"))
    )
    (net (code "18") (name "LCD_DATA") (class "Default")
      (node (ref "U$1") (pin "P$5") (pinfunction "PA7_P$5") (pintype "bidirectional"))
      (node (ref "U$10") (pin "P$31") (pinfunction "D3/SDA_P$31") (pintype "bidirectional"))
    )
    (net (code "19") (name "LCD_RESET") (class "Default")
      (node (ref "U$1") (pin "P$8") (pinfunction "PB0_P$8") (pintype "bidirectional"))
      (node (ref "U$10") (pin "P$29") (pinfunction "RST_P$29") (pintype "bidirectional"))
    )
    (net (code "20") (name "Net-(C1-P$1)") (class "Default")
      (node (ref "C1") (pin "1") (pinfunction "P$1_1") (pintype "passive"))
      (node (ref "D1") (pin "C") (pinfunction "C_C") (pintype "passive"))
      (node (ref "U$10") (pin "P$1") (pinfunction "A1+_P$1") (pintype "bidirectional"))
    )
    (net (code "21") (name "Net-(C6-P$1)") (class "Default")
      (node (ref "C6") (pin "1") (pinfunction "P$1_1") (pintype "passive"))
      (node (ref "U$10") (pin "P$20") (pinfunction "VB1-_P$20") (pintype "bidirectional"))
    )
    (net (code "22") (name "Net-(C6-P$2)") (class "Default")
      (node (ref "C6") (pin "2") (pinfunction "P$2_2") (pintype "passive"))
      (node (ref "U$10") (pin "P$19") (pinfunction "VB1+_P$19") (pintype "bidirectional"))
    )
    (net (code "23") (name "Net-(C7-P$1)") (class "Default")
      (node (ref "C7") (pin "1") (pinfunction "P$1_1") (pintype "passive"))
      (node (ref "U$10") (pin "P$21") (pinfunction "VB0-_P$21") (pintype "bidirectional"))
    )
    (net (code "24") (name "Net-(C7-P$2)") (class "Default")
      (node (ref "C7") (pin "2") (pinfunction "P$2_2") (pintype "passive"))
      (node (ref "U$10") (pin "P$18") (pinfunction "VB0+_P$18") (pintype "bidirectional"))
    )
    (net (code "25") (name "Net-(C8-P$2)") (class "Default")
      (node (ref "C8") (pin "2") (pinfunction "P$2_2") (pintype "passive"))
      (node (ref "R9") (pin "2") (pinfunction "2_2") (pintype "passive"))
      (node (ref "U$10") (pin "P$17") (pinfunction "VLCD_P$17") (pintype "bidirectional"))
    )
    (net (code "26") (name "Net-(IC1-FB)") (class "Default")
      (node (ref "IC1") (pin "4") (pinfunction "FB_4") (pintype "input"))
      (node (ref "R2") (pin "1") (pinfunction "1_1") (pintype "passive"))
      (node (ref "R3") (pin "2") (pinfunction "2_2") (pintype "passive"))
    )
    (net (code "27") (name "Net-(IC1-OUT)") (class "Default")
      (node (ref "D2") (pin "C") (pinfunction "C_C") (pintype "passive"))
      (node (ref "IC1") (pin "2") (pinfunction "OUT_2") (pintype "output"))
      (node (ref "L2") (pin "1") (pinfunction "1_1") (pintype "passive"))
    )
    (net (code "28") (name "Net-(LED1-BGND)") (class "Default")
      (node (ref "LED1") (pin "1") (pinfunction "BGND_1") (pintype "power_in"))
      (node (ref "U$30") (pin "8") (pinfunction "/OUT2_8") (pintype "bidirectional"))
    )
    (net (code "29") (name "Net-(LED1-GGND)") (class "Default")
      (node (ref "LED1") (pin "2") (pinfunction "GGND_2") (pintype "power_in"))
      (node (ref "U$30") (pin "7") (pinfunction "/OUT1_7") (pintype "bidirectional"))
    )
    (net (code "30") (name "Net-(LED1-RGND)") (class "Default")
      (node (ref "LED1") (pin "3") (pinfunction "RGND_3") (pintype "power_in"))
      (node (ref "U$30") (pin "6") (pinfunction "/OUT0_6") (pintype "bidirectional"))
    )
    (net (code "31") (name "Net-(LED2-BGND)") (class "Default")
      (node (ref "LED2") (pin "1") (pinfunction "BGND_1") (pintype "power_in"))
      (node (ref "U$30") (pin "12") (pinfunction "/OUT5_12") (pintype "bidirectional"))
    )
    (net (code "32") (name "Net-(LED2-GGND)") (class "Default")
      (node (ref "LED2") (pin "2") (pinfunction "GGND_2") (pintype "power_in"))
      (node (ref "U$30") (pin "11") (pinfunction "/OUT4_11") (pintype "bidirectional"))
    )
    (net (code "33") (name "Net-(LED2-RGND)") (class "Default")
      (node (ref "LED2") (pin "3") (pinfunction "RGND_3") (pintype "power_in"))
      (node (ref "U$30") (pin "9") (pinfunction "/OUT3_9") (pintype "bidirectional"))
    )
    (net (code "34") (name "Net-(LED3-BGND)") (class "Default")
      (node (ref "LED3") (pin "1") (pinfunction "BGND_1") (pintype "power_in"))
      (node (ref "U$30") (pin "15") (pinfunction "/OUT8_15") (pintype "bidirectional"))
    )
    (net (code "35") (name "Net-(LED3-GGND)") (class "Default")
      (node (ref "LED3") (pin "2") (pinfunction "GGND_2") (pintype "power_in"))
      (node (ref "U$30") (pin "14") (pinfunction "/OUT7_14") (pintype "bidirectional"))
    )
    (net (code "36") (name "Net-(LED3-RGND)") (class "Default")
      (node (ref "LED3") (pin "3") (pinfunction "RGND_3") (pintype "power_in"))
      (node (ref "U$30") (pin "13") (pinfunction "/OUT6_13") (pintype "bidirectional"))
    )
    (net (code "37") (name "Net-(LED4-BGND)") (class "Default")
      (node (ref "LED4") (pin "1") (pinfunction "BGND_1") (pintype "power_in"))
      (node (ref "U$30") (pin "18") (pinfunction "/OUT11_18") (pintype "bidirectional"))
    )
    (net (code "38") (name "Net-(LED4-GGND)") (class "Default")
      (node (ref "LED4") (pin "2") (pinfunction "GGND_2") (pintype "power_in"))
      (node (ref "U$30") (pin "17") (pinfunction "/OUT10_17") (pintype "bidirectional"))
    )
    (net (code "39") (name "Net-(LED4-RGND)") (class "Default")
      (node (ref "LED4") (pin "3") (pinfunction "RGND_3") (pintype "power_in"))
      (node (ref "U$30") (pin "16") (pinfunction "/OUT9_16") (pintype "bidirectional"))
    )
    (net (code "40") (name "Net-(LED5-BGND)") (class "Default")
      (node (ref "LED5") (pin "1") (pinfunction "BGND_1") (pintype "power_in"))
      (node (ref "U$30") (pin "22") (pinfunction "/OUT14_22") (pintype "bidirectional"))
    )
    (net (code "41") (name "Net-(LED5-GGND)") (class "Default")
      (node (ref "LED5") (pin "2") (pinfunction "GGND_2") (pintype "power_in"))
      (node (ref "U$30") (pin "21") (pinfunction "/OUT13_21") (pintype "bidirectional"))
    )
    (net (code "42") (name "Net-(LED5-RGND)") (class "Default")
      (node (ref "LED5") (pin "3") (pinfunction "RGND_3") (pintype "power_in"))
      (node (ref "U$30") (pin "20") (pinfunction "/OUT12_20") (pintype "bidirectional"))
    )
    (net (code "43") (name "Net-(LED6-BGND)") (class "Default")
      (node (ref "LED6") (pin "1") (pinfunction "BGND_1") (pintype "power_in"))
      (node (ref "U$33") (pin "8") (pinfunction "/OUT2_8") (pintype "bidirectional"))
    )
    (net (code "44") (name "Net-(LED6-GGND)") (class "Default")
      (node (ref "LED6") (pin "2") (pinfunction "GGND_2") (pintype "power_in"))
      (node (ref "U$33") (pin "7") (pinfunction "/OUT1_7") (pintype "bidirectional"))
    )
    (net (code "45") (name "Net-(LED6-RGND)") (class "Default")
      (node (ref "LED6") (pin "3") (pinfunction "RGND_3") (pintype "power_in"))
      (node (ref "U$33") (pin "6") (pinfunction "/OUT0_6") (pintype "bidirectional"))
    )
    (net (code "46") (name "Net-(LED7-BGND)") (class "Default")
      (node (ref "LED7") (pin "1") (pinfunction "BGND_1") (pintype "power_in"))
      (node (ref "U$33") (pin "12") (pinfunction "/OUT5_12") (pintype "bidirectional"))
    )
    (net (code "47") (name "Net-(LED7-GGND)") (class "Default")
      (node (ref "LED7") (pin "2") (pinfunction "GGND_2") (pintype "power_in"))
      (node (ref "U$33") (pin "11") (pinfunction "/OUT4_11") (pintype "bidirectional"))
    )
    (net (code "48") (name "Net-(LED7-RGND)") (class "Default")
      (node (ref "LED7") (pin "3") (pinfunction "RGND_3") (pintype "power_in"))
      (node (ref "U$33") (pin "9") (pinfunction "/OUT3_9") (pintype "bidirectional"))
    )
    (net (code "49") (name "Net-(LED8-BGND)") (class "Default")
      (node (ref "LED8") (pin "1") (pinfunction "BGND_1") (pintype "power_in"))
      (node (ref "U$33") (pin "15") (pinfunction "/OUT8_15") (pintype "bidirectional"))
    )
    (net (code "50") (name "Net-(LED8-GGND)") (class "Default")
      (node (ref "LED8") (pin "2") (pinfunction "GGND_2") (pintype "power_in"))
      (node (ref "U$33") (pin "14") (pinfunction "/OUT7_14") (pintype "bidirectional"))
    )
    (net (code "51") (name "Net-(LED8-RGND)") (class "Default")
      (node (ref "LED8") (pin "3") (pinfunction "RGND_3") (pintype "power_in"))
      (node (ref "U$33") (pin "13") (pinfunction "/OUT6_13") (pintype "bidirectional"))
    )
    (net (code "52") (name "Net-(LED9-BGND)") (class "Default")
      (node (ref "LED9") (pin "1") (pinfunction "BGND_1") (pintype "power_in"))
      (node (ref "U$33") (pin "18") (pinfunction "/OUT11_18") (pintype "bidirectional"))
    )
    (net (code "53") (name "Net-(LED9-GGND)") (class "Default")
      (node (ref "LED9") (pin "2") (pinfunction "GGND_2") (pintype "power_in"))
      (node (ref "U$33") (pin "17") (pinfunction "/OUT10_17") (pintype "bidirectional"))
    )
    (net (code "54") (name "Net-(LED9-RGND)") (class "Default")
      (node (ref "LED9") (pin "3") (pinfunction "RGND_3") (pintype "power_in"))
      (node (ref "U$33") (pin "16") (pinfunction "/OUT9_16") (pintype "bidirectional"))
    )
    (net (code "55") (name "Net-(LED10-BGND)") (class "Default")
      (node (ref "LED10") (pin "1") (pinfunction "BGND_1") (pintype "power_in"))
      (node (ref "U$33") (pin "22") (pinfunction "/OUT14_22") (pintype "bidirectional"))
    )
    (net (code "56") (name "Net-(LED10-GGND)") (class "Default")
      (node (ref "LED10") (pin "2") (pinfunction "GGND_2") (pintype "power_in"))
      (node (ref "U$33") (pin "21") (pinfunction "/OUT13_21") (pintype "bidirectional"))
    )
    (net (code "57") (name "Net-(LED10-RGND)") (class "Default")
      (node (ref "LED10") (pin "3") (pinfunction "RGND_3") (pintype "power_in"))
      (node (ref "U$33") (pin "20") (pinfunction "/OUT12_20") (pintype "bidirectional"))
    )
    (net (code "58") (name "Net-(LED11-BGND)") (class "Default")
      (node (ref "LED11") (pin "1") (pinfunction "BGND_1") (pintype "power_in"))
      (node (ref "U$36") (pin "8") (pinfunction "/OUT2_8") (pintype "bidirectional"))
    )
    (net (code "59") (name "Net-(LED11-GGND)") (class "Default")
      (node (ref "LED11") (pin "2") (pinfunction "GGND_2") (pintype "power_in"))
      (node (ref "U$36") (pin "7") (pinfunction "/OUT1_7") (pintype "bidirectional"))
    )
    (net (code "60") (name "Net-(LED11-RGND)") (class "Default")
      (node (ref "LED11") (pin "3") (pinfunction "RGND_3") (pintype "power_in"))
      (node (ref "U$36") (pin "6") (pinfunction "/OUT0_6") (pintype "bidirectional"))
    )
    (net (code "61") (name "Net-(LED12-BGND)") (class "Default")
      (node (ref "LED12") (pin "1") (pinfunction "BGND_1") (pintype "power_in"))
      (node (ref "U$36") (pin "12") (pinfunction "/OUT5_12") (pintype "bidirectional"))
    )
    (net (code "62") (name "Net-(LED12-GGND)") (class "Default")
      (node (ref "LED12") (pin "2") (pinfunction "GGND_2") (pintype "power_in"))
      (node (ref "U$36") (pin "11") (pinfunction "/OUT4_11") (pintype "bidirectional"))
    )
    (net (code "63") (name "Net-(LED12-RGND)") (class "Default")
      (node (ref "LED12") (pin "3") (pinfunction "RGND_3") (pintype "power_in"))
      (node (ref "U$36") (pin "9") (pinfunction "/OUT3_9") (pintype "bidirectional"))
    )
    (net (code "64") (name "Net-(LED13-BGND)") (class "Default")
      (node (ref "LED13") (pin "1") (pinfunction "BGND_1") (pintype "power_in"))
      (node (ref "U$36") (pin "15") (pinfunction "/OUT8_15") (pintype "bidirectional"))
    )
    (net (code "65") (name "Net-(LED13-GGND)") (class "Default")
      (node (ref "LED13") (pin "2") (pinfunction "GGND_2") (pintype "power_in"))
      (node (ref "U$36") (pin "14") (pinfunction "/OUT7_14") (pintype "bidirectional"))
    )
    (net (code "66") (name "Net-(LED13-RGND)") (class "Default")
      (node (ref "LED13") (pin "3") (pinfunction "RGND_3") (pintype "power_in"))
      (node (ref "U$36") (pin "13") (pinfunction "/OUT6_13") (pintype "bidirectional"))
    )
    (net (code "67") (name "Net-(LED14-BGND)") (class "Default")
      (node (ref "LED14") (pin "1") (pinfunction "BGND_1") (pintype "power_in"))
      (node (ref "U$36") (pin "18") (pinfunction "/OUT11_18") (pintype "bidirectional"))
    )
    (net (code "68") (name "Net-(LED14-GGND)") (class "Default")
      (node (ref "LED14") (pin "2") (pinfunction "GGND_2") (pintype "power_in"))
      (node (ref "U$36") (pin "17") (pinfunction "/OUT10_17") (pintype "bidirectional"))
    )
    (net (code "69") (name "Net-(LED14-RGND)") (class "Default")
      (node (ref "LED14") (pin "3") (pinfunction "RGND_3") (pintype "power_in"))
      (node (ref "U$36") (pin "16") (pinfunction "/OUT9_16") (pintype "bidirectional"))
    )
    (net (code "70") (name "Net-(LED15-BGND)") (class "Default")
      (node (ref "LED15") (pin "1") (pinfunction "BGND_1") (pintype "power_in"))
      (node (ref "U$36") (pin "22") (pinfunction "/OUT14_22") (pintype "bidirectional"))
    )
    (net (code "71") (name "Net-(LED15-GGND)") (class "Default")
      (node (ref "LED15") (pin "2") (pinfunction "GGND_2") (pintype "power_in"))
      (node (ref "U$36") (pin "21") (pinfunction "/OUT13_21") (pintype "bidirectional"))
    )
    (net (code "72") (name "Net-(LED15-RGND)") (class "Default")
      (node (ref "LED15") (pin "3") (pinfunction "RGND_3") (pintype "power_in"))
      (node (ref "U$36") (pin "20") (pinfunction "/OUT12_20") (pintype "bidirectional"))
    )
    (net (code "73") (name "Net-(LED16-BGND)") (class "Default")
      (node (ref "LED16") (pin "1") (pinfunction "BGND_1") (pintype "power_in"))
      (node (ref "U$51") (pin "8") (pinfunction "/OUT2_8") (pintype "bidirectional"))
    )
    (net (code "74") (name "Net-(LED16-GGND)") (class "Default")
      (node (ref "LED16") (pin "2") (pinfunction "GGND_2") (pintype "power_in"))
      (node (ref "U$51") (pin "7") (pinfunction "/OUT1_7") (pintype "bidirectional"))
    )
    (net (code "75") (name "Net-(LED16-RGND)") (class "Default")
      (node (ref "LED16") (pin "3") (pinfunction "RGND_3") (pintype "power_in"))
      (node (ref "U$51") (pin "6") (pinfunction "/OUT0_6") (pintype "bidirectional"))
    )
    (net (code "76") (name "Net-(LED17-BGND)") (class "Default")
      (node (ref "LED17") (pin "1") (pinfunction "BGND_1") (pintype "power_in"))
      (node (ref "U$51") (pin "12") (pinfunction "/OUT5_12") (pintype "bidirectional"))
    )
    (net (code "77") (name "Net-(LED17-GGND)") (class "Default")
      (node (ref "LED17") (pin "2") (pinfunction "GGND_2") (pintype "power_in"))
      (node (ref "U$51") (pin "11") (pinfunction "/OUT4_11") (pintype "bidirectional"))
    )
    (net (code "78") (name "Net-(LED17-RGND)") (class "Default")
      (node (ref "LED17") (pin "3") (pinfunction "RGND_3") (pintype "power_in"))
      (node (ref "U$51") (pin "9") (pinfunction "/OUT3_9") (pintype "bidirectional"))
    )
    (net (code "79") (name "Net-(LED18-BGND)") (class "Default")
      (node (ref "LED18") (pin "1") (pinfunction "BGND_1") (pintype "power_in"))
      (node (ref "U$51") (pin "15") (pinfunction "/OUT8_15") (pintype "bidirectional"))
    )
    (net (code "80") (name "Net-(LED18-GGND)") (class "Default")
      (node (ref "LED18") (pin "2") (pinfunction "GGND_2") (pintype "power_in"))
      (node (ref "U$51") (pin "14") (pinfunction "/OUT7_14") (pintype "bidirectional"))
    )
    (net (code "81") (name "Net-(LED18-RGND)") (class "Default")
      (node (ref "LED18") (pin "3") (pinfunction "RGND_3") (pintype "power_in"))
      (node (ref "U$51") (pin "13") (pinfunction "/OUT6_13") (pintype "bidirectional"))
    )
    (net (code "82") (name "Net-(LED19-BGND)") (class "Default")
      (node (ref "LED19") (pin "1") (pinfunction "BGND_1") (pintype "power_in"))
      (node (ref "U$51") (pin "18") (pinfunction "/OUT11_18") (pintype "bidirectional"))
    )
    (net (code "83") (name "Net-(LED19-GGND)") (class "Default")
      (node (ref "LED19") (pin "2") (pinfunction "GGND_2") (pintype "power_in"))
      (node (ref "U$51") (pin "17") (pinfunction "/OUT10_17") (pintype "bidirectional"))
    )
    (net (code "84") (name "Net-(LED19-RGND)") (class "Default")
      (node (ref "LED19") (pin "3") (pinfunction "RGND_3") (pintype "power_in"))
      (node (ref "U$51") (pin "16") (pinfunction "/OUT9_16") (pintype "bidirectional"))
    )
    (net (code "85") (name "Net-(LED20-BGND)") (class "Default")
      (node (ref "LED20") (pin "1") (pinfunction "BGND_1") (pintype "power_in"))
      (node (ref "U$51") (pin "22") (pinfunction "/OUT14_22") (pintype "bidirectional"))
    )
    (net (code "86") (name "Net-(LED20-GGND)") (class "Default")
      (node (ref "LED20") (pin "2") (pinfunction "GGND_2") (pintype "power_in"))
      (node (ref "U$51") (pin "21") (pinfunction "/OUT13_21") (pintype "bidirectional"))
    )
    (net (code "87") (name "Net-(LED20-RGND)") (class "Default")
      (node (ref "LED20") (pin "3") (pinfunction "RGND_3") (pintype "power_in"))
      (node (ref "U$51") (pin "20") (pinfunction "/OUT12_20") (pintype "bidirectional"))
    )
    (net (code "88") (name "Net-(U$10-A2+)") (class "Default")
      (node (ref "U$10") (pin "P$14") (pinfunction "C1-_P$14") (pintype "bidirectional"))
      (node (ref "U$10") (pin "P$2") (pinfunction "A2+_P$2") (pintype "bidirectional"))
    )
    (net (code "89") (name "Net-(U$10-A3+)") (class "Default")
      (node (ref "U$10") (pin "P$15") (pinfunction "C2-_P$15") (pintype "bidirectional"))
      (node (ref "U$10") (pin "P$3") (pinfunction "A3+_P$3") (pintype "bidirectional"))
    )
    (net (code "90") (name "Net-(U$10-C3-)") (class "Default")
      (node (ref "R1") (pin "1") (pinfunction "1_1") (pintype "passive"))
      (node (ref "U$10") (pin "P$16") (pinfunction "C3-_P$16") (pintype "bidirectional"))
      (node (ref "U1") (pin "3") (pinfunction "FB_3") (pintype "bidirectional"))
    )
    (net (code "91") (name "Net-(U$30-REXT)") (class "Default")
      (node (ref "R4") (pin "1") (pinfunction "1_1") (pintype "passive"))
      (node (ref "U$30") (pin "1") (pinfunction "REXT_1") (pintype "bidirectional"))
    )
    (net (code "92") (name "Net-(U$33-REXT)") (class "Default")
      (node (ref "R5") (pin "1") (pinfunction "1_1") (pintype "passive"))
      (node (ref "U$33") (pin "1") (pinfunction "REXT_1") (pintype "bidirectional"))
    )
    (net (code "93") (name "Net-(U$36-REXT)") (class "Default")
      (node (ref "R6") (pin "1") (pinfunction "1_1") (pintype "passive"))
      (node (ref "U$36") (pin "1") (pinfunction "REXT_1") (pintype "bidirectional"))
    )
    (net (code "94") (name "Net-(U$51-REXT)") (class "Default")
      (node (ref "R15") (pin "1") (pinfunction "1_1") (pintype "passive"))
      (node (ref "U$51") (pin "1") (pinfunction "REXT_1") (pintype "bidirectional"))
    )
    (net (code "95") (name "Net-(U1-SW)") (class "Default")
      (node (ref "D1") (pin "A") (pinfunction "A_A") (pintype "passive"))
      (node (ref "L1") (pin "1") (pinfunction "1_1") (pintype "passive"))
      (node (ref "U1") (pin "1") (pinfunction "SW_1") (pintype "bidirectional"))
    )
    (net (code "96") (name "SCL") (class "Default")
      (node (ref "R8") (pin "1") (pinfunction "1_1") (pintype "passive"))
      (node (ref "U$1") (pin "P$21") (pinfunction "PB10_P$21") (pintype "bidirectional"))
      (node (ref "U$30") (pin "26") (pinfunction "SCL_26") (pintype "bidirectional"))
      (node (ref "U$33") (pin "26") (pinfunction "SCL_26") (pintype "bidirectional"))
      (node (ref "U$36") (pin "26") (pinfunction "SCL_26") (pintype "bidirectional"))
      (node (ref "U$51") (pin "26") (pinfunction "SCL_26") (pintype "bidirectional"))
    )
    (net (code "97") (name "SDA") (class "Default")
      (node (ref "R7") (pin "1") (pinfunction "1_1") (pintype "passive"))
      (node (ref "U$1") (pin "P$22") (pinfunction "PB11_P$22") (pintype "bidirectional"))
      (node (ref "U$30") (pin "27") (pinfunction "SDA_27") (pintype "bidirectional"))
      (node (ref "U$33") (pin "27") (pinfunction "SDA_27") (pintype "bidirectional"))
      (node (ref "U$36") (pin "27") (pinfunction "SDA_27") (pintype "bidirectional"))
      (node (ref "U$51") (pin "27") (pinfunction "SDA_27") (pintype "bidirectional"))
    )
    (net (code "98") (name "SW1") (class "Default")
      (node (ref "C22") (pin "2") (pinfunction "P$2_2") (pintype "passive"))
      (node (ref "IC3") (pin "1") (pinfunction "I_1") (pintype "input"))
      (node (ref "R16") (pin "1") (pinfunction "1_1") (pintype "passive"))
      (node (ref "S1") (pin "3") (pinfunction "P_3") (pintype "passive"))
      (node (ref "S1") (pin "4") (pinfunction "P1_4") (pintype "passive"))
    )
    (net (code "99") (name "SW1S") (class "Default")
      (node (ref "IC3") (pin "2") (pinfunction "O_2") (pintype "output"))
      (node (ref "U$1") (pin "P$11") (pinfunction "PE8_P$11") (pintype "bidirectional"))
    )
    (net (code "100") (name "SW2") (class "Default")
      (node (ref "C23") (pin "2") (pinfunction "P$2_2") (pintype "passive"))
      (node (ref "IC3") (pin "3") (pinfunction "I_3") (pintype "input"))
      (node (ref "R17") (pin "1") (pinfunction "1_1") (pintype "passive"))
      (node (ref "S2") (pin "3") (pinfunction "P_3") (pintype "passive"))
      (node (ref "S2") (pin "4") (pinfunction "P1_4") (pintype "passive"))
    )
    (net (code "101") (name "SW2S") (class "Default")
      (node (ref "IC3") (pin "4") (pinfunction "O_4") (pintype "output"))
      (node (ref "U$1") (pin "P$9") (pinfunction "PB1_P$9") (pintype "bidirectional"))
    )
    (net (code "102") (name "SW3") (class "Default")
      (node (ref "C20") (pin "2") (pinfunction "P$2_2") (pintype "passive"))
      (node (ref "IC3") (pin "11") (pinfunction "I_11") (pintype "input"))
      (node (ref "R18") (pin "1") (pinfunction "1_1") (pintype "passive"))
      (node (ref "S3") (pin "3") (pinfunction "P_3") (pintype "passive"))
      (node (ref "S3") (pin "4") (pinfunction "P1_4") (pintype "passive"))
    )
    (net (code "103") (name "SW3S") (class "Default")
      (node (ref "IC3") (pin "10") (pinfunction "O_10") (pintype "output"))
      (node (ref "U$1") (pin "P$15") (pinfunction "PE12_P$15") (pintype "bidirectional"))
    )
    (net (code "104") (name "SW4") (class "Default")
      (node (ref "C19") (pin "2") (pinfunction "P$2_2") (pintype "passive"))
      (node (ref "IC3") (pin "13") (pinfunction "I_13") (pintype "input"))
      (node (ref "R19") (pin "1") (pinfunction "1_1") (pintype "passive"))
      (node (ref "S4") (pin "3") (pinfunction "P_3") (pintype "passive"))
      (node (ref "S4") (pin "4") (pinfunction "P1_4") (pintype "passive"))
    )
    (net (code "105") (name "SW4S") (class "Default")
      (node (ref "IC3") (pin "12") (pinfunction "O_12") (pintype "output"))
      (node (ref "U$1") (pin "P$13") (pinfunction "PE10_P$13") (pintype "bidirectional"))
    )
    (net (code "106") (name "SW5") (class "Default")
      (node (ref "C21") (pin "2") (pinfunction "P$2_2") (pintype "passive"))
      (node (ref "IC3") (pin "9") (pinfunction "I_9") (pintype "input"))
      (node (ref "R20") (pin "1") (pinfunction "1_1") (pintype "passive"))
      (node (ref "S5") (pin "3") (pinfunction "P_3") (pintype "passive"))
      (node (ref "S5") (pin "4") (pinfunction "P1_4") (pintype "passive"))
    )
    (net (code "107") (name "SW5S") (class "Default")
      (node (ref "IC3") (pin "8") (pinfunction "O_8") (pintype "output"))
      (node (ref "U$1") (pin "P$17") (pinfunction "PE14_P$17") (pintype "bidirectional"))
    )
    (net (code "108") (name "SW6") (class "Default")
      (node (ref "C4") (pin "2") (pinfunction "P$2_2") (pintype "passive"))
      (node (ref "IC3") (pin "5") (pinfunction "I_5") (pintype "input"))
      (node (ref "R21") (pin "1") (pinfunction "1_1") (pintype "passive"))
      (node (ref "S6") (pin "3") (pinfunction "P_3") (pintype "passive"))
      (node (ref "S6") (pin "4") (pinfunction "P1_4") (pintype "passive"))
    )
    (net (code "109") (name "SW6S") (class "Default")
      (node (ref "IC3") (pin "6") (pinfunction "O_6") (pintype "output"))
      (node (ref "U$1") (pin "P$10") (pinfunction "PE7_P$10") (pintype "bidirectional"))
    )
    (net (code "110") (name "VSUP") (class "Default")
      (node (ref "C25") (pin "+") (pinfunction "+_+") (pintype "passive"))
      (node (ref "IC1") (pin "1") (pinfunction "IN_1") (pintype "input"))
      (node (ref "PTC1") (pin "P$1") (pinfunction "1_P$1") (pintype "passive"))
      (node (ref "TP1") (pin "P$1") (pinfunction "P$1_P$1") (pintype "bidirectional"))
    )
    (net (code "111") (name "unconnected-(IC2F-O-Pad6)") (class "Default")
      (node (ref "IC2") (pin "6") (pinfunction "O_6") (pintype "output"))
    )
    (net (code "112") (name "unconnected-(U$1A-PA4-PadP$2)") (class "Default")
      (node (ref "U$1") (pin "P$2") (pinfunction "PA4_P$2") (pintype "bidirectional"))
    )
    (net (code "113") (name "unconnected-(U$1A-PA6-PadP$4)") (class "Default")
      (node (ref "U$1") (pin "P$4") (pinfunction "PA6_P$4") (pintype "bidirectional"))
    )
    (net (code "114") (name "unconnected-(U$1A-PE9-PadP$12)") (class "Default")
      (node (ref "U$1") (pin "P$12") (pinfunction "PE9_P$12") (pintype "bidirectional"))
    )
    (net (code "115") (name "unconnected-(U$1A-PE11-PadP$14)") (class "Default")
      (node (ref "U$1") (pin "P$14") (pinfunction "PE11_P$14") (pintype "bidirectional"))
    )
    (net (code "116") (name "unconnected-(U$1A-PE13-PadP$16)") (class "Default")
      (node (ref "U$1") (pin "P$16") (pinfunction "PE13_P$16") (pintype "bidirectional"))
    )
    (net (code "117") (name "unconnected-(U$1A-PE15-PadP$18)") (class "Default")
      (node (ref "U$1") (pin "P$18") (pinfunction "PE15_P$18") (pintype "bidirectional"))
    )
    (net (code "118") (name "unconnected-(U$1B-PA8-PadP$39)") (class "Default")
      (node (ref "U$1") (pin "P$39") (pinfunction "PA8_P$39") (pintype "bidirectional"))
    )
    (net (code "119") (name "unconnected-(U$1B-PA9-PadP$40)") (class "Default")
      (node (ref "U$1") (pin "P$40") (pinfunction "PA9_P$40") (pintype "bidirectional"))
    )
    (net (code "120") (name "unconnected-(U$1B-PB12-PadP$23)") (class "Default")
      (node (ref "U$1") (pin "P$23") (pinfunction "PB12_P$23") (pintype "bidirectional"))
    )
    (net (code "121") (name "unconnected-(U$1B-PB14-PadP$25)") (class "Default")
      (node (ref "U$1") (pin "P$25") (pinfunction "PB14_P$25") (pintype "bidirectional"))
    )
    (net (code "122") (name "unconnected-(U$1B-PC7-PadP$36)") (class "Default")
      (node (ref "U$1") (pin "P$36") (pinfunction "PC7_P$36") (pintype "bidirectional"))
    )
    (net (code "123") (name "unconnected-(U$1B-PC8-PadP$37)") (class "Default")
      (node (ref "U$1") (pin "P$37") (pinfunction "PC8_P$37") (pintype "bidirectional"))
    )
    (net (code "124") (name "unconnected-(U$1B-PC9-PadP$38)") (class "Default")
      (node (ref "U$1") (pin "P$38") (pinfunction "PC9_P$38") (pintype "bidirectional"))
    )
    (net (code "125") (name "unconnected-(U$1B-PD8-PadP$27)") (class "Default")
      (node (ref "U$1") (pin "P$27") (pinfunction "PD8_P$27") (pintype "bidirectional"))
    )
    (net (code "126") (name "unconnected-(U$1B-PD10-PadP$29)") (class "Default")
      (node (ref "U$1") (pin "P$29") (pinfunction "PD10_P$29") (pintype "bidirectional"))
    )
    (net (code "127") (name "unconnected-(U$1B-PD12-PadP$31)") (class "Default")
      (node (ref "U$1") (pin "P$31") (pinfunction "PD12_P$31") (pintype "bidirectional"))
    )
    (net (code "128") (name "unconnected-(U$1B-PD13-PadP$32)") (class "Default")
      (node (ref "U$1") (pin "P$32") (pinfunction "PD13_P$32") (pintype "bidirectional"))
    )
    (net (code "129") (name "unconnected-(U$1B-PD14-PadP$33)") (class "Default")
      (node (ref "U$1") (pin "P$33") (pinfunction "PD14_P$33") (pintype "bidirectional"))
    )
    (net (code "130") (name "unconnected-(U$1B-PD15-PadP$34)") (class "Default")
      (node (ref "U$1") (pin "P$34") (pinfunction "PD15_P$34") (pintype "bidirectional"))
    )
    (net (code "131") (name "unconnected-(U$1C-PB4-PadP$54)") (class "Default")
      (node (ref "U$1") (pin "P$54") (pinfunction "PB4_P$54") (pintype "bidirectional"))
    )
    (net (code "132") (name "unconnected-(U$1C-PB5-PadP$55)") (class "Default")
      (node (ref "U$1") (pin "P$55") (pinfunction "PB5_P$55") (pintype "bidirectional"))
    )
    (net (code "133") (name "unconnected-(U$1C-PB6-PadP$56)") (class "Default")
      (node (ref "U$1") (pin "P$56") (pinfunction "PB6_P$56") (pintype "bidirectional"))
    )
    (net (code "134") (name "unconnected-(U$1C-PB7-PadP$57)") (class "Default")
      (node (ref "U$1") (pin "P$57") (pinfunction "PB7_P$57") (pintype "bidirectional"))
    )
    (net (code "135") (name "unconnected-(U$1C-PB8-PadP$58)") (class "Default")
      (node (ref "U$1") (pin "P$58") (pinfunction "PB8_P$58") (pintype "bidirectional"))
    )
    (net (code "136") (name "unconnected-(U$1C-PB9-PadP$59)") (class "Default")
      (node (ref "U$1") (pin "P$59") (pinfunction "PB9_P$59") (pintype "bidirectional"))
    )
    (net (code "137") (name "unconnected-(U$1C-PC10-PadP$45)") (class "Default")
      (node (ref "U$1") (pin "P$45") (pinfunction "PC10_P$45") (pintype "bidirectional"))
    )
    (net (code "138") (name "unconnected-(U$1C-PC11-PadP$46)") (class "Default")
      (node (ref "U$1") (pin "P$46") (pinfunction "PC11_P$46") (pintype "bidirectional"))
    )
    (net (code "139") (name "unconnected-(U$1C-PC12-PadP$47)") (class "Default")
      (node (ref "U$1") (pin "P$47") (pinfunction "PC12_P$47") (pintype "bidirectional"))
    )
    (net (code "140") (name "unconnected-(U$1C-PD2-PadP$48)") (class "Default")
      (node (ref "U$1") (pin "P$48") (pinfunction "PD2_P$48") (pintype "bidirectional"))
    )
    (net (code "141") (name "unconnected-(U$1C-PD3-PadP$49)") (class "Default")
      (node (ref "U$1") (pin "P$49") (pinfunction "PD3_P$49") (pintype "bidirectional"))
    )
    (net (code "142") (name "unconnected-(U$1C-PD4-PadP$50)") (class "Default")
      (node (ref "U$1") (pin "P$50") (pinfunction "PD4_P$50") (pintype "bidirectional"))
    )
    (net (code "143") (name "unconnected-(U$1C-PD5-PadP$51)") (class "Default")
      (node (ref "U$1") (pin "P$51") (pinfunction "PD5_P$51") (pintype "bidirectional"))
    )
    (net (code "144") (name "unconnected-(U$1C-PD6-PadP$52)") (class "Default")
      (node (ref "U$1") (pin "P$52") (pinfunction "PD6_P$52") (pintype "bidirectional"))
    )
    (net (code "145") (name "unconnected-(U$1C-PD7-PadP$53)") (class "Default")
      (node (ref "U$1") (pin "P$53") (pinfunction "PD7_P$53") (pintype "bidirectional"))
    )
    (net (code "146") (name "unconnected-(U$1C-PE0-PadP$60)") (class "Default")
      (node (ref "U$1") (pin "P$60") (pinfunction "PE0_P$60") (pintype "bidirectional"))
    )
    (net (code "147") (name "unconnected-(U$1C-PE1-PadP$61)") (class "Default")
      (node (ref "U$1") (pin "P$61") (pinfunction "PE1_P$61") (pintype "bidirectional"))
    )
    (net (code "148") (name "unconnected-(U$1D-PA0-PadP$75)") (class "Default")
      (node (ref "U$1") (pin "P$75") (pinfunction "PA0_P$75") (pintype "bidirectional"))
    )
    (net (code "149") (name "unconnected-(U$1D-PA1-PadP$76)") (class "Default")
      (node (ref "U$1") (pin "P$76") (pinfunction "PA1_P$76") (pintype "bidirectional"))
    )
    (net (code "150") (name "unconnected-(U$1D-PA2-PadP$77)") (class "Default")
      (node (ref "U$1") (pin "P$77") (pinfunction "PA2_P$77") (pintype "bidirectional"))
    )
    (net (code "151") (name "unconnected-(U$1D-PC0-PadP$71)") (class "Default")
      (node (ref "U$1") (pin "P$71") (pinfunction "PC0_P$71") (pintype "bidirectional"))
    )
    (net (code "152") (name "unconnected-(U$1D-PC1-PadP$72)") (class "Default")
      (node (ref "U$1") (pin "P$72") (pinfunction "PC1_P$72") (pintype "bidirectional"))
    )
    (net (code "153") (name "unconnected-(U$1D-PC2-PadP$73)") (class "Default")
      (node (ref "U$1") (pin "P$73") (pinfunction "PC2_P$73") (pintype "bidirectional"))
    )
    (net (code "154") (name "unconnected-(U$1D-PC3-PadP$74)") (class "Default")
      (node (ref "U$1") (pin "P$74") (pinfunction "PC3_P$74") (pintype "bidirectional"))
    )
    (net (code "155") (name "unconnected-(U$1D-PC13-PadP$68)") (class "Default")
      (node (ref "U$1") (pin "P$68") (pinfunction "PC13_P$68") (pintype "bidirectional"))
    )
    (net (code "156") (name "unconnected-(U$1D-PE2-PadP$63)") (class "Default")
      (node (ref "U$1") (pin "P$63") (pinfunction "PE2_P$63") (pintype "bidirectional"))
    )
    (net (code "157") (name "unconnected-(U$1D-PE3-PadP$64)") (class "Default")
      (node (ref "U$1") (pin "P$64") (pinfunction "PE3_P$64") (pintype "bidirectional"))
    )
    (net (code "158") (name "unconnected-(U$1D-PE4-PadP$65)") (class "Default")
      (node (ref "U$1") (pin "P$65") (pinfunction "PE4_P$65") (pintype "bidirectional"))
    )
    (net (code "159") (name "unconnected-(U$1D-PE5-PadP$66)") (class "Default")
      (node (ref "U$1") (pin "P$66") (pinfunction "PE5_P$66") (pintype "bidirectional"))
    )
    (net (code "160") (name "unconnected-(U$1D-PE6-PadP$67)") (class "Default")
      (node (ref "U$1") (pin "P$67") (pinfunction "PE6_P$67") (pintype "bidirectional"))
    )
    (net (code "161") (name "unconnected-(U$30-{slash}OUT15-Pad23)") (class "Default")
      (node (ref "U$30") (pin "23") (pinfunction "/OUT15_23") (pintype "bidirectional"))
    )
    (net (code "162") (name "unconnected-(U$33-{slash}OUT15-Pad23)") (class "Default")
      (node (ref "U$33") (pin "23") (pinfunction "/OUT15_23") (pintype "bidirectional"))
    )
    (net (code "163") (name "unconnected-(U$36-{slash}OUT15-Pad23)") (class "Default")
      (node (ref "U$36") (pin "23") (pinfunction "/OUT15_23") (pintype "bidirectional"))
    )
    (net (code "164") (name "unconnected-(U$51-{slash}OUT15-Pad23)") (class "Default")
      (node (ref "U$51") (pin "23") (pinfunction "/OUT15_23") (pintype "bidirectional"))
    )
  )
)
